# UserInterface_0.net
KiCad netlist of a schematic drawn in Altium Designer
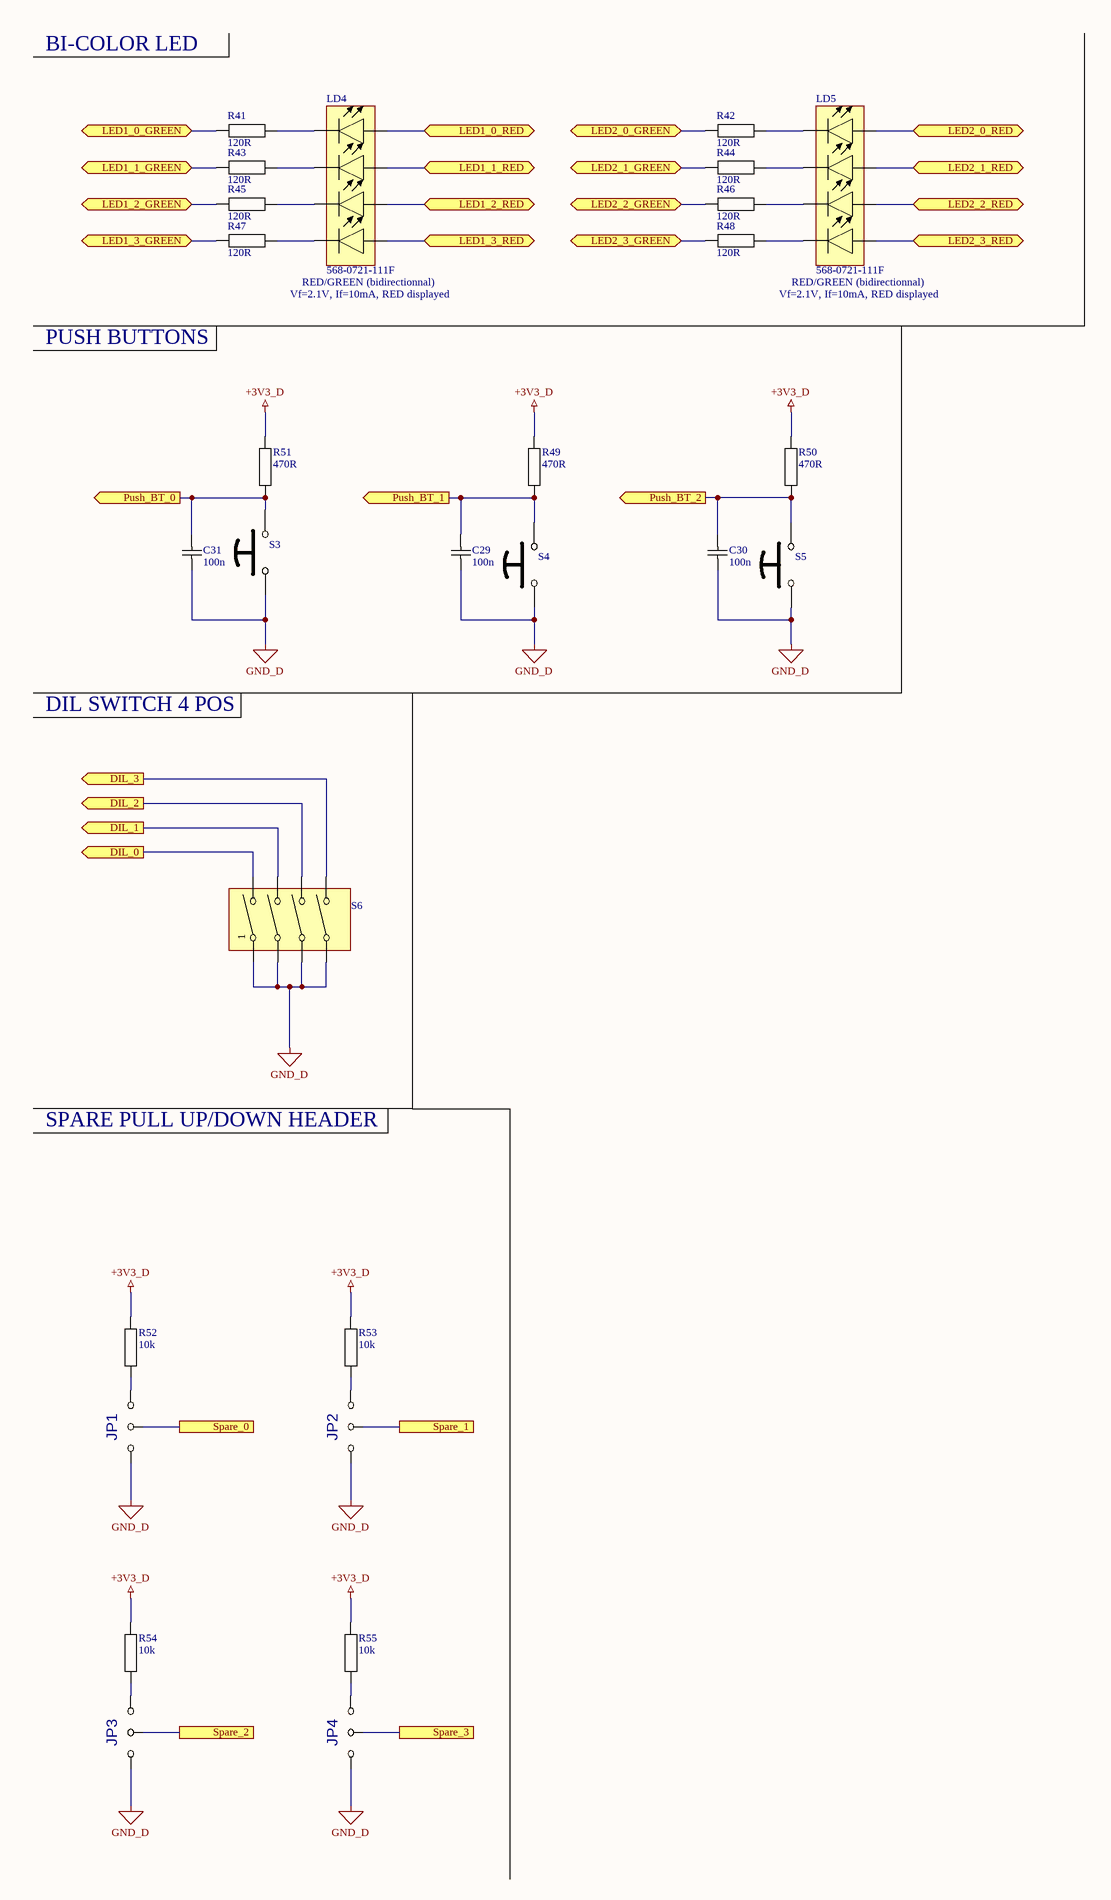
[diagram p0: UserInterface_0.SchDoc, left]
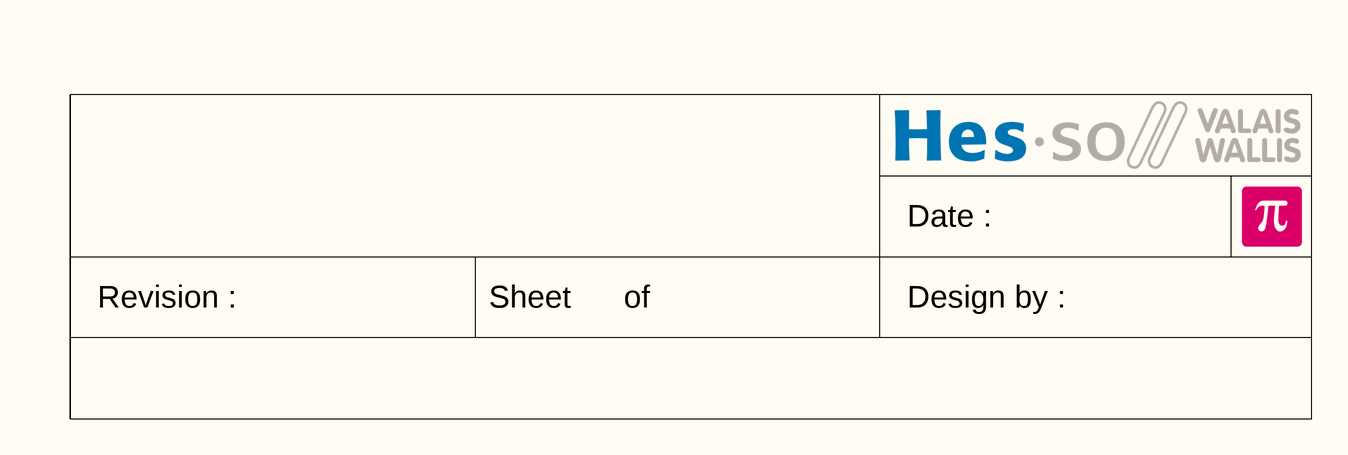
[diagram p1: UserInterface_0.SchDoc, right]

(export (version "E")
  (design (tool "Eeschema 10.0.6"))
  (components
    (comp (ref "C29")
      (value "100n")
      (footprint "CAPACITOR 1608 REFLOW")
      (description "Capacitor X7R 10% 50V 2012(0805)")
      (libsource (lib "Capacitor") (part "Capacitor"))
    )
    (comp (ref "C30")
      (value "100n")
      (footprint "CAPACITOR 1608 REFLOW")
      (description "Capacitor X7R 10% 50V 2012(0805)")
      (libsource (lib "Capacitor") (part "Capacitor"))
    )
    (comp (ref "C31")
      (value "100n")
      (footprint "CAPACITOR 1608 REFLOW")
      (description "Capacitor X7R 10% 50V 2012(0805)")
      (libsource (lib "Capacitor") (part "Capacitor"))
    )
    (comp (ref "JP1")
      (value "{Value}")
      (footprint "JUMPER3 SMD 2012")
      (description "JUMPER 3 POS")
      (libsource (lib "Jumper") (part "JUMPER 3 POS"))
    )
    (comp (ref "JP2")
      (value "{Value}")
      (footprint "JUMPER3 SMD 2012")
      (description "JUMPER 3 POS")
      (libsource (lib "Jumper") (part "JUMPER 3 POS"))
    )
    (comp (ref "JP3")
      (value "{Value}")
      (footprint "JUMPER3 SMD 2012")
      (description "JUMPER 3 POS")
      (libsource (lib "Jumper") (part "JUMPER 3 POS"))
    )
    (comp (ref "JP4")
      (value "{Value}")
      (footprint "JUMPER3 SMD 2012")
      (description "JUMPER 3 POS")
      (libsource (lib "Jumper") (part "JUMPER 3 POS"))
    )
    (comp (ref "LD4")
      (value "568-0721-111F")
      (footprint "LED Dialight 568-0721-111")
      (description "LED Dialight 568-0721-111F")
      (fields (field (name "MANUFACTURER") "Dialight"))
      (libsource (lib "Diode") (part "LED Dialight 568-0721-111F"))
    )
    (comp (ref "LD5")
      (value "568-0721-111F")
      (footprint "LED Dialight 568-0721-111")
      (description "LED Dialight 568-0721-111F")
      (fields (field (name "MANUFACTURER") "Dialight"))
      (libsource (lib "Diode") (part "LED Dialight 568-0721-111F"))
    )
    (comp (ref "R41")
      (value "120R")
      (footprint "RESISTOR 1608 REFLOW")
      (description "Resistor 1% 50V 100mW 1608(0603)")
      (libsource (lib "Resistor") (part "Resistor"))
    )
    (comp (ref "R42")
      (value "120R")
      (footprint "RESISTOR 1608 REFLOW")
      (description "Resistor 1% 50V 100mW 1608(0603)")
      (libsource (lib "Resistor") (part "Resistor"))
    )
    (comp (ref "R43")
      (value "120R")
      (footprint "RESISTOR 1608 REFLOW")
      (description "Resistor 1% 50V 100mW 1608(0603)")
      (libsource (lib "Resistor") (part "Resistor"))
    )
    (comp (ref "R44")
      (value "120R")
      (footprint "RESISTOR 1608 REFLOW")
      (description "Resistor 1% 50V 100mW 1608(0603)")
      (libsource (lib "Resistor") (part "Resistor"))
    )
    (comp (ref "R45")
      (value "120R")
      (footprint "RESISTOR 1608 REFLOW")
      (description "Resistor 1% 50V 100mW 1608(0603)")
      (libsource (lib "Resistor") (part "Resistor"))
    )
    (comp (ref "R46")
      (value "120R")
      (footprint "RESISTOR 1608 REFLOW")
      (description "Resistor 1% 50V 100mW 1608(0603)")
      (libsource (lib "Resistor") (part "Resistor"))
    )
    (comp (ref "R47")
      (value "120R")
      (footprint "RESISTOR 1608 REFLOW")
      (description "Resistor 1% 50V 100mW 1608(0603)")
      (libsource (lib "Resistor") (part "Resistor"))
    )
    (comp (ref "R48")
      (value "120R")
      (footprint "RESISTOR 1608 REFLOW")
      (description "Resistor 1% 50V 100mW 1608(0603)")
      (libsource (lib "Resistor") (part "Resistor"))
    )
    (comp (ref "R49")
      (value "470R")
      (footprint "RESISTOR 1608 REFLOW")
      (description "Resistor 1% 50V 125mW 2012(0805)")
      (libsource (lib "Resistor") (part "Resistor"))
    )
    (comp (ref "R50")
      (value "470R")
      (footprint "RESISTOR 1608 REFLOW")
      (description "Resistor 1% 50V 125mW 2012(0805)")
      (libsource (lib "Resistor") (part "Resistor"))
    )
    (comp (ref "R51")
      (value "470R")
      (footprint "RESISTOR 1608 REFLOW")
      (description "Resistor 1% 50V 125mW 2012(0805)")
      (libsource (lib "Resistor") (part "Resistor"))
    )
    (comp (ref "R52")
      (value "10k")
      (footprint "RESISTOR 1608 REFLOW")
      (description "Resistor 1% 50V 125mW 2012(0805)")
      (libsource (lib "Resistor") (part "Resistor"))
    )
    (comp (ref "R53")
      (value "10k")
      (footprint "RESISTOR 1608 REFLOW")
      (description "Resistor 1% 50V 125mW 2012(0805)")
      (libsource (lib "Resistor") (part "Resistor"))
    )
    (comp (ref "R54")
      (value "10k")
      (footprint "RESISTOR 1608 REFLOW")
      (description "Resistor 1% 50V 125mW 2012(0805)")
      (libsource (lib "Resistor") (part "Resistor"))
    )
    (comp (ref "R55")
      (value "10k")
      (footprint "RESISTOR 1608 REFLOW")
      (description "Resistor 1% 50V 125mW 2012(0805)")
      (libsource (lib "Resistor") (part "Resistor"))
    )
    (comp (ref "S3")
      (value "FSMRA4JH04")
      (footprint "Push Button C7.1x3.7 TE FSMRA4JH")
      (description "Push Button, 2 pins")
      (fields (field (name "MANUFACTURER") "TE Connectivity / Alcoswitch"))
      (libsource (lib "Button") (part "Push Button 2Pins"))
    )
    (comp (ref "S4")
      (value "FSMRA4JH04")
      (footprint "Push Button C7.1x3.7 TE FSMRA4JH")
      (description "Push Button, 2 pins")
      (fields (field (name "MANUFACTURER") "TE Connectivity / Alcoswitch"))
      (libsource (lib "Button") (part "Push Button 2Pins"))
    )
    (comp (ref "S5")
      (value "FSMRA4JH04")
      (footprint "Push Button C7.1x3.7 TE FSMRA4JH")
      (description "Push Button, 2 pins")
      (fields (field (name "MANUFACTURER") "TE Connectivity / Alcoswitch"))
      (libsource (lib "Button") (part "Push Button 2Pins"))
    )
    (comp (ref "S6")
      (value "*")
      (footprint "DIP SWITCH MULTICOMP  MCDHN-04F")
      (description "MULTICOMP  MCDHN-04F")
      (libsource (lib "Button") (part "DIP Switch 4Pos"))
    )
  )
  (nets
    (net (code "1") (name "+3V3_D") (class "Default")
      (node (ref "R49") (pin "2") (pinfunction "2_2") (pintype "passive"))
      (node (ref "R50") (pin "2") (pinfunction "2_2") (pintype "passive"))
      (node (ref "R51") (pin "2") (pinfunction "2_2") (pintype "passive"))
      (node (ref "R52") (pin "2") (pinfunction "2_2") (pintype "passive"))
      (node (ref "R53") (pin "2") (pinfunction "2_2") (pintype "passive"))
      (node (ref "R54") (pin "2") (pinfunction "2_2") (pintype "passive"))
      (node (ref "R55") (pin "2") (pinfunction "2_2") (pintype "passive"))
    )
    (net (code "2") (name "/DIL_0") (class "Default")
      (node (ref "S6") (pin "2") (pinfunction "2_2") (pintype "passive"))
    )
    (net (code "3") (name "/DIL_1") (class "Default")
      (node (ref "S6") (pin "4") (pinfunction "4_4") (pintype "passive"))
    )
    (net (code "4") (name "/DIL_2") (class "Default")
      (node (ref "S6") (pin "6") (pinfunction "6_6") (pintype "passive"))
    )
    (net (code "5") (name "/DIL_3") (class "Default")
      (node (ref "S6") (pin "8") (pinfunction "8_8") (pintype "passive"))
    )
    (net (code "6") (name "/LED1_0_GREEN") (class "Default")
      (node (ref "R41") (pin "1") (pinfunction "1_1") (pintype "passive"))
    )
    (net (code "7") (name "/LED1_0_RED") (class "Default")
      (node (ref "LD4") (pin "8") (pinfunction "A_8") (pintype "passive"))
    )
    (net (code "8") (name "/LED1_1_GREEN") (class "Default")
      (node (ref "R43") (pin "1") (pinfunction "1_1") (pintype "passive"))
    )
    (net (code "9") (name "/LED1_1_RED") (class "Default")
      (node (ref "LD4") (pin "6") (pinfunction "A_6") (pintype "passive"))
    )
    (net (code "10") (name "/LED1_2_GREEN") (class "Default")
      (node (ref "R45") (pin "1") (pinfunction "1_1") (pintype "passive"))
    )
    (net (code "11") (name "/LED1_2_RED") (class "Default")
      (node (ref "LD4") (pin "4") (pinfunction "A_4") (pintype "passive"))
    )
    (net (code "12") (name "/LED1_3_GREEN") (class "Default")
      (node (ref "R47") (pin "1") (pinfunction "1_1") (pintype "passive"))
    )
    (net (code "13") (name "/LED1_3_RED") (class "Default")
      (node (ref "LD4") (pin "2") (pinfunction "A_2") (pintype "passive"))
    )
    (net (code "14") (name "/LED2_0_GREEN") (class "Default")
      (node (ref "R42") (pin "1") (pinfunction "1_1") (pintype "passive"))
    )
    (net (code "15") (name "/LED2_0_RED") (class "Default")
      (node (ref "LD5") (pin "8") (pinfunction "A_8") (pintype "passive"))
    )
    (net (code "16") (name "/LED2_1_GREEN") (class "Default")
      (node (ref "R44") (pin "1") (pinfunction "1_1") (pintype "passive"))
    )
    (net (code "17") (name "/LED2_1_RED") (class "Default")
      (node (ref "LD5") (pin "6") (pinfunction "A_6") (pintype "passive"))
    )
    (net (code "18") (name "/LED2_2_GREEN") (class "Default")
      (node (ref "R46") (pin "1") (pinfunction "1_1") (pintype "passive"))
    )
    (net (code "19") (name "/LED2_2_RED") (class "Default")
      (node (ref "LD5") (pin "4") (pinfunction "A_4") (pintype "passive"))
    )
    (net (code "20") (name "/LED2_3_GREEN") (class "Default")
      (node (ref "R48") (pin "1") (pinfunction "1_1") (pintype "passive"))
    )
    (net (code "21") (name "/LED2_3_RED") (class "Default")
      (node (ref "LD5") (pin "2") (pinfunction "A_2") (pintype "passive"))
    )
    (net (code "22") (name "/Push_BT_0") (class "Default")
      (node (ref "C31") (pin "2") (pinfunction "2_2") (pintype "passive"))
      (node (ref "R51") (pin "1") (pinfunction "1_1") (pintype "passive"))
      (node (ref "S3") (pin "2") (pinfunction "2_2") (pintype "passive"))
    )
    (net (code "23") (name "/Push_BT_1") (class "Default")
      (node (ref "C29") (pin "2") (pinfunction "2_2") (pintype "passive"))
      (node (ref "R49") (pin "1") (pinfunction "1_1") (pintype "passive"))
      (node (ref "S4") (pin "2") (pinfunction "2_2") (pintype "passive"))
    )
    (net (code "24") (name "/Push_BT_2") (class "Default")
      (node (ref "C30") (pin "2") (pinfunction "2_2") (pintype "passive"))
      (node (ref "R50") (pin "1") (pinfunction "1_1") (pintype "passive"))
      (node (ref "S5") (pin "2") (pinfunction "2_2") (pintype "passive"))
    )
    (net (code "25") (name "/Spare_0") (class "Default")
      (node (ref "JP1") (pin "2") (pinfunction "2_2") (pintype "passive"))
    )
    (net (code "26") (name "/Spare_1") (class "Default")
      (node (ref "JP2") (pin "2") (pinfunction "2_2") (pintype "passive"))
    )
    (net (code "27") (name "/Spare_2") (class "Default")
      (node (ref "JP3") (pin "2") (pinfunction "2_2") (pintype "passive"))
    )
    (net (code "28") (name "/Spare_3") (class "Default")
      (node (ref "JP4") (pin "2") (pinfunction "2_2") (pintype "passive"))
    )
    (net (code "29") (name "GND_D") (class "Default")
      (node (ref "C29") (pin "1") (pinfunction "1_1") (pintype "passive"))
      (node (ref "C30") (pin "1") (pinfunction "1_1") (pintype "passive"))
      (node (ref "C31") (pin "1") (pinfunction "1_1") (pintype "passive"))
      (node (ref "JP1") (pin "1") (pinfunction "1_1") (pintype "passive"))
      (node (ref "JP2") (pin "1") (pinfunction "1_1") (pintype "passive"))
      (node (ref "JP3") (pin "1") (pinfunction "1_1") (pintype "passive"))
      (node (ref "JP4") (pin "1") (pinfunction "1_1") (pintype "passive"))
      (node (ref "S3") (pin "1") (pinfunction "1_1") (pintype "passive"))
      (node (ref "S4") (pin "1") (pinfunction "1_1") (pintype "passive"))
      (node (ref "S5") (pin "1") (pinfunction "1_1") (pintype "passive"))
      (node (ref "S6") (pin "1") (pinfunction "1_1") (pintype "passive"))
      (node (ref "S6") (pin "3") (pinfunction "3_3") (pintype "passive"))
      (node (ref "S6") (pin "5") (pinfunction "5_5") (pintype "passive"))
      (node (ref "S6") (pin "7") (pinfunction "7_7") (pintype "passive"))
    )
    (net (code "30") (name "Net-(JP1-Pad3)") (class "Default")
      (node (ref "JP1") (pin "3") (pinfunction "3_3") (pintype "passive"))
      (node (ref "R52") (pin "1") (pinfunction "1_1") (pintype "passive"))
    )
    (net (code "31") (name "Net-(JP2-Pad3)") (class "Default")
      (node (ref "JP2") (pin "3") (pinfunction "3_3") (pintype "passive"))
      (node (ref "R53") (pin "1") (pinfunction "1_1") (pintype "passive"))
    )
    (net (code "32") (name "Net-(JP3-Pad3)") (class "Default")
      (node (ref "JP3") (pin "3") (pinfunction "3_3") (pintype "passive"))
      (node (ref "R54") (pin "1") (pinfunction "1_1") (pintype "passive"))
    )
    (net (code "33") (name "Net-(JP4-Pad3)") (class "Default")
      (node (ref "JP4") (pin "3") (pinfunction "3_3") (pintype "passive"))
      (node (ref "R55") (pin "1") (pinfunction "1_1") (pintype "passive"))
    )
    (net (code "34") (name "Net-(LD4-C-Pad1)") (class "Default")
      (node (ref "LD4") (pin "1") (pinfunction "C_1") (pintype "passive"))
      (node (ref "R47") (pin "2") (pinfunction "2_2") (pintype "passive"))
    )
    (net (code "35") (name "Net-(LD4-C-Pad3)") (class "Default")
      (node (ref "LD4") (pin "3") (pinfunction "C_3") (pintype "passive"))
      (node (ref "R45") (pin "2") (pinfunction "2_2") (pintype "passive"))
    )
    (net (code "36") (name "Net-(LD4-C-Pad5)") (class "Default")
      (node (ref "LD4") (pin "5") (pinfunction "C_5") (pintype "passive"))
      (node (ref "R43") (pin "2") (pinfunction "2_2") (pintype "passive"))
    )
    (net (code "37") (name "Net-(LD4-C-Pad7)") (class "Default")
      (node (ref "LD4") (pin "7") (pinfunction "C_7") (pintype "passive"))
      (node (ref "R41") (pin "2") (pinfunction "2_2") (pintype "passive"))
    )
    (net (code "38") (name "Net-(LD5-C-Pad1)") (class "Default")
      (node (ref "LD5") (pin "1") (pinfunction "C_1") (pintype "passive"))
      (node (ref "R48") (pin "2") (pinfunction "2_2") (pintype "passive"))
    )
    (net (code "39") (name "Net-(LD5-C-Pad3)") (class "Default")
      (node (ref "LD5") (pin "3") (pinfunction "C_3") (pintype "passive"))
      (node (ref "R46") (pin "2") (pinfunction "2_2") (pintype "passive"))
    )
    (net (code "40") (name "Net-(LD5-C-Pad5)") (class "Default")
      (node (ref "LD5") (pin "5") (pinfunction "C_5") (pintype "passive"))
      (node (ref "R44") (pin "2") (pinfunction "2_2") (pintype "passive"))
    )
    (net (code "41") (name "Net-(LD5-C-Pad7)") (class "Default")
      (node (ref "LD5") (pin "7") (pinfunction "C_7") (pintype "passive"))
      (node (ref "R42") (pin "2") (pinfunction "2_2") (pintype "passive"))
    )
  )
)
